# touche_client.net
KiCad netlist of a schematic drawn in EAGLE
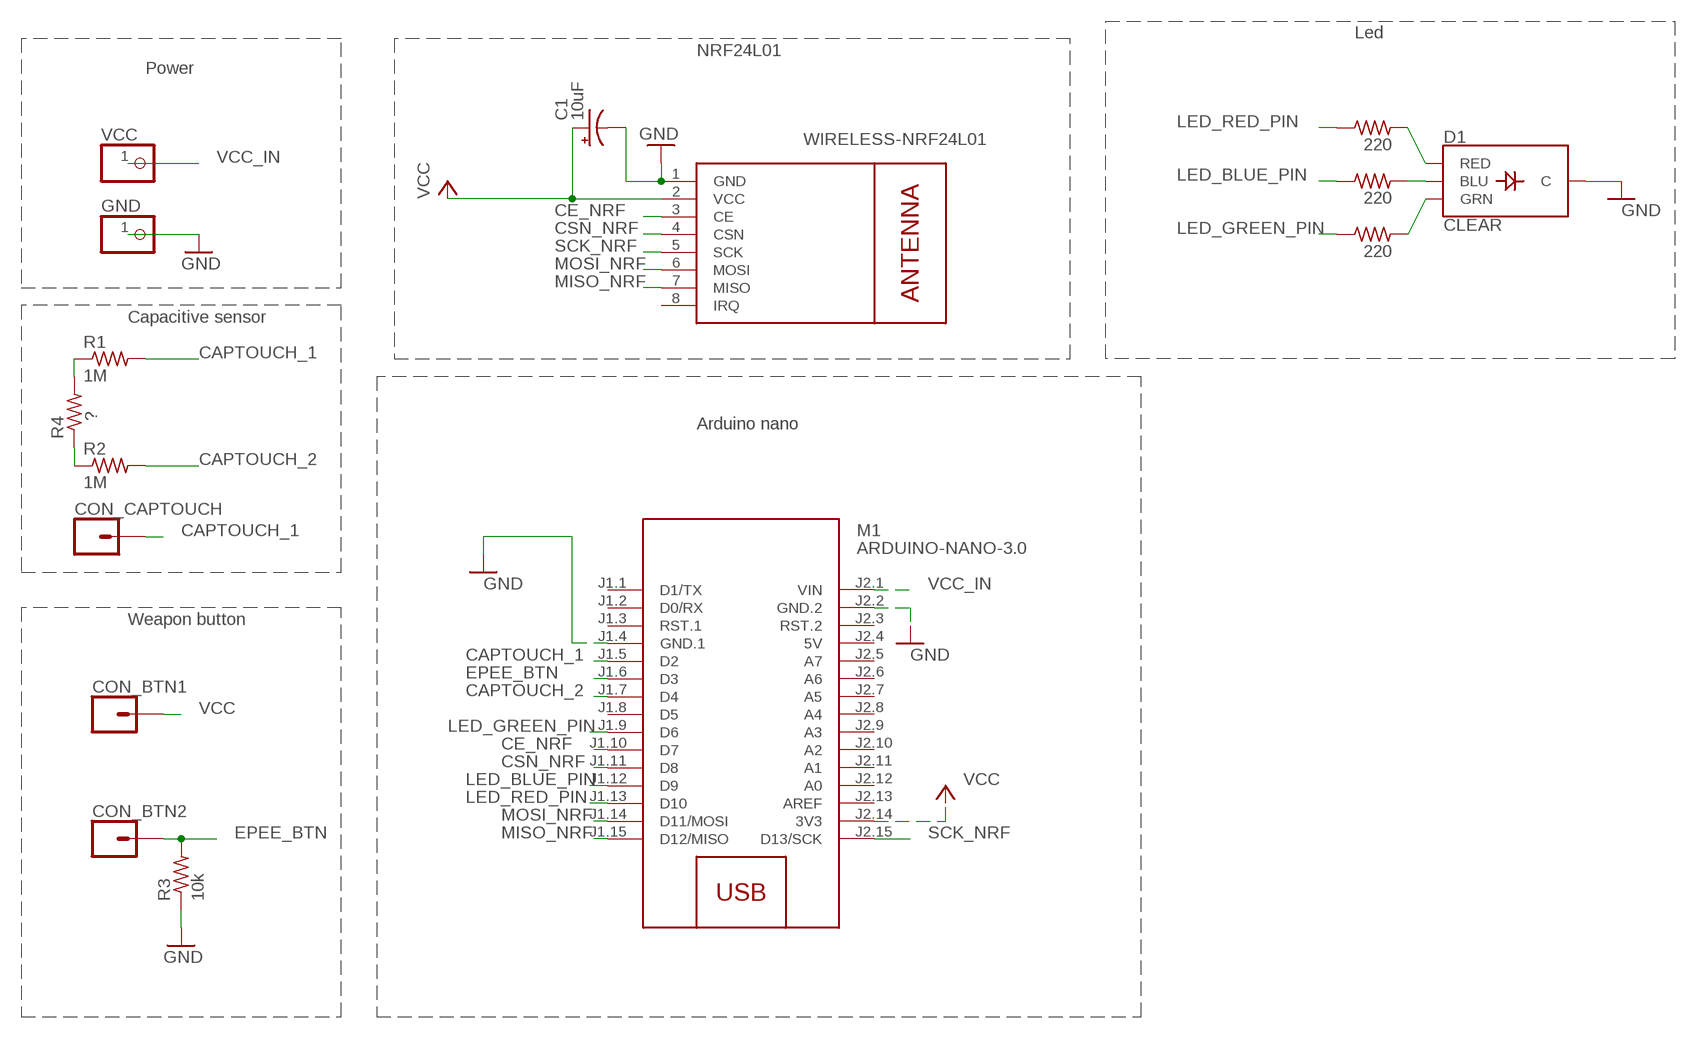
[diagram p0: schematic, sheet 1]

(export (version "E")
  (design (tool "Eeschema 10.0.6"))
  (components
    (comp (ref "C1")
      (value "10uF")
      (footprint "eagle-import:E2-5")
      (libsource (lib "eagle-import") (part "CPOL-USE2-5"))
    )
    (comp (ref "CON_BTN1")
      (value "CONN_01")
      (footprint "eagle-import:1X01")
      (libsource (lib "eagle-import") (part "CONN_01"))
    )
    (comp (ref "CON_BTN2")
      (value "CONN_01")
      (footprint "eagle-import:1X01")
      (libsource (lib "eagle-import") (part "CONN_01"))
    )
    (comp (ref "CON_CAPTOUCH")
      (value "CONN_01")
      (footprint "eagle-import:1X01")
      (libsource (lib "eagle-import") (part "CONN_01"))
    )
    (comp (ref "D1")
      (value "CLEAR")
      (footprint "eagle-import:LED-RGB-THRU")
      (libsource (lib "eagle-import") (part "LED-RGB-CCCLEAR"))
    )
    (comp (ref "GND")
      (value "PINHD-1X1")
      (footprint "eagle-import:1X01")
      (libsource (lib "eagle-import") (part "PINHD-1X1"))
    )
    (comp (ref "M1")
      (value "ARDUINO-NANO-3.0")
      (footprint "eagle-import:ARDUINO-NANO-3.0")
      (libsource (lib "eagle-import") (part "ARDUINO-NANO-3.0"))
    )
    (comp (ref "M2")
      (value "WIRELESS-NRF24L01")
      (footprint "eagle-import:WIRELESS-NRF24L01")
      (libsource (lib "eagle-import") (part "WIRELESS-NRF24L01"))
    )
    (comp (ref "R1")
      (value "1M")
      (footprint "eagle-import:0204_7")
      (libsource (lib "eagle-import") (part "R-US_0204/7"))
    )
    (comp (ref "R2")
      (value "1M")
      (footprint "eagle-import:0204_7")
      (libsource (lib "eagle-import") (part "R-US_0204/7"))
    )
    (comp (ref "R3")
      (value "10k")
      (footprint "eagle-import:0204_7")
      (libsource (lib "eagle-import") (part "R-US_0204/7"))
    )
    (comp (ref "R4")
      (value "?")
      (footprint "eagle-import:0204_7")
      (libsource (lib "eagle-import") (part "R-US_0204/7"))
    )
    (comp (ref "R_LED1")
      (value "220")
      (footprint "eagle-import:0204_7")
      (libsource (lib "eagle-import") (part "R-US_0204/7"))
    )
    (comp (ref "R_LED2")
      (value "220")
      (footprint "eagle-import:0204_7")
      (libsource (lib "eagle-import") (part "R-US_0204/7"))
    )
    (comp (ref "R_LED3")
      (value "220")
      (footprint "eagle-import:0204_7")
      (libsource (lib "eagle-import") (part "R-US_0204/7"))
    )
    (comp (ref "VCC")
      (value "PINHD-1X1")
      (footprint "eagle-import:1X01")
      (libsource (lib "eagle-import") (part "PINHD-1X1"))
    )
  )
  (nets
    (net (code "1") (name "/5V") (class "Default")
      (node (ref "M1") (pin "J2.4") (pinfunction "5V_J2.4") (pintype "power_in"))
    )
    (net (code "2") (name "/CAPTOUCH_1") (class "Default")
      (node (ref "CON_CAPTOUCH") (pin "1") (pinfunction "1_1") (pintype "passive"))
      (node (ref "M1") (pin "J1.5") (pinfunction "D2_J1.5") (pintype "bidirectional"))
      (node (ref "R1") (pin "2") (pinfunction "2_2") (pintype "passive"))
    )
    (net (code "3") (name "/CAPTOUCH_2") (class "Default")
      (node (ref "M1") (pin "J1.7") (pinfunction "D4_J1.7") (pintype "bidirectional"))
      (node (ref "R2") (pin "2") (pinfunction "2_2") (pintype "passive"))
    )
    (net (code "4") (name "/CE_NRF") (class "Default")
      (node (ref "M1") (pin "J1.10") (pinfunction "D7_J1.10") (pintype "bidirectional"))
      (node (ref "M2") (pin "3") (pinfunction "CE_3") (pintype "bidirectional"))
    )
    (net (code "5") (name "/CSN_NRF") (class "Default")
      (node (ref "M1") (pin "J1.11") (pinfunction "D8_J1.11") (pintype "bidirectional"))
      (node (ref "M2") (pin "4") (pinfunction "CSN_4") (pintype "bidirectional"))
    )
    (net (code "6") (name "/EPEE_BTN") (class "Default")
      (node (ref "CON_BTN2") (pin "1") (pinfunction "1_1") (pintype "passive"))
      (node (ref "M1") (pin "J1.6") (pinfunction "D3_J1.6") (pintype "bidirectional"))
      (node (ref "R3") (pin "2") (pinfunction "2_2") (pintype "passive"))
    )
    (net (code "7") (name "/LED_BLUE_PIN") (class "Default")
      (node (ref "M1") (pin "J1.12") (pinfunction "D9_J1.12") (pintype "bidirectional"))
      (node (ref "R_LED2") (pin "1") (pinfunction "1_1") (pintype "passive"))
    )
    (net (code "8") (name "/LED_GREEN_PIN") (class "Default")
      (node (ref "M1") (pin "J1.9") (pinfunction "D6_J1.9") (pintype "bidirectional"))
      (node (ref "R_LED3") (pin "1") (pinfunction "1_1") (pintype "passive"))
    )
    (net (code "9") (name "/LED_RED_PIN") (class "Default")
      (node (ref "M1") (pin "J1.13") (pinfunction "D10_J1.13") (pintype "bidirectional"))
      (node (ref "R_LED1") (pin "1") (pinfunction "1_1") (pintype "passive"))
    )
    (net (code "10") (name "/MISO_NRF") (class "Default")
      (node (ref "M1") (pin "J1.15") (pinfunction "D12/MISO_J1.15") (pintype "bidirectional"))
      (node (ref "M2") (pin "7") (pinfunction "MISO_7") (pintype "bidirectional"))
    )
    (net (code "11") (name "/MOSI_NRF") (class "Default")
      (node (ref "M1") (pin "J1.14") (pinfunction "D11/MOSI_J1.14") (pintype "bidirectional"))
      (node (ref "M2") (pin "6") (pinfunction "MOSI_6") (pintype "bidirectional"))
    )
    (net (code "12") (name "/SCK_NRF") (class "Default")
      (node (ref "M1") (pin "J2.15") (pinfunction "D13/SCK_J2.15") (pintype "bidirectional"))
      (node (ref "M2") (pin "5") (pinfunction "SCK_5") (pintype "bidirectional"))
    )
    (net (code "13") (name "/VCC_IN") (class "Default")
      (node (ref "M1") (pin "J2.1") (pinfunction "VIN_J2.1") (pintype "power_in"))
      (node (ref "VCC") (pin "1") (pinfunction "1_1") (pintype "passive"))
    )
    (net (code "14") (name "GND") (class "Default")
      (node (ref "C1") (pin "-") (pinfunction "-_-") (pintype "passive"))
      (node (ref "D1") (pin "2") (pinfunction "C_2") (pintype "bidirectional"))
      (node (ref "GND") (pin "1") (pinfunction "1_1") (pintype "passive"))
      (node (ref "M1") (pin "J1.4") (pinfunction "GND.1_J1.4") (pintype "power_in"))
      (node (ref "M1") (pin "J2.2") (pinfunction "GND.2_J2.2") (pintype "power_in"))
      (node (ref "M2") (pin "1") (pinfunction "GND_1") (pintype "power_in"))
      (node (ref "R3") (pin "1") (pinfunction "1_1") (pintype "passive"))
    )
    (net (code "15") (name "Net-(D1-BLU)") (class "Default")
      (node (ref "D1") (pin "4") (pinfunction "BLU_4") (pintype "bidirectional"))
      (node (ref "R_LED2") (pin "2") (pinfunction "2_2") (pintype "passive"))
    )
    (net (code "16") (name "Net-(D1-GRN)") (class "Default")
      (node (ref "D1") (pin "3") (pinfunction "GRN_3") (pintype "bidirectional"))
      (node (ref "R_LED3") (pin "2") (pinfunction "2_2") (pintype "passive"))
    )
    (net (code "17") (name "Net-(D1-RED)") (class "Default")
      (node (ref "D1") (pin "1") (pinfunction "RED_1") (pintype "bidirectional"))
      (node (ref "R_LED1") (pin "2") (pinfunction "2_2") (pintype "passive"))
    )
    (net (code "18") (name "Net-(R1-Pad1)") (class "Default")
      (node (ref "R1") (pin "1") (pinfunction "1_1") (pintype "passive"))
      (node (ref "R4") (pin "2") (pinfunction "2_2") (pintype "passive"))
    )
    (net (code "19") (name "Net-(R2-Pad1)") (class "Default")
      (node (ref "R2") (pin "1") (pinfunction "1_1") (pintype "passive"))
      (node (ref "R4") (pin "1") (pinfunction "1_1") (pintype "passive"))
    )
    (net (code "20") (name "VCC") (class "Default")
      (node (ref "C1") (pin "+") (pinfunction "+_+") (pintype "passive"))
      (node (ref "CON_BTN1") (pin "1") (pinfunction "1_1") (pintype "passive"))
      (node (ref "M1") (pin "J2.14") (pinfunction "3V3_J2.14") (pintype "power_in"))
      (node (ref "M2") (pin "2") (pinfunction "VCC_2") (pintype "power_in"))
    )
    (net (code "21") (name "unconnected-(M1-A0-PadJ2.12)") (class "Default")
      (node (ref "M1") (pin "J2.12") (pinfunction "A0_J2.12") (pintype "bidirectional"))
    )
    (net (code "22") (name "unconnected-(M1-A1-PadJ2.11)") (class "Default")
      (node (ref "M1") (pin "J2.11") (pinfunction "A1_J2.11") (pintype "bidirectional"))
    )
    (net (code "23") (name "unconnected-(M1-A2-PadJ2.10)") (class "Default")
      (node (ref "M1") (pin "J2.10") (pinfunction "A2_J2.10") (pintype "bidirectional"))
    )
    (net (code "24") (name "unconnected-(M1-A3-PadJ2.9)") (class "Default")
      (node (ref "M1") (pin "J2.9") (pinfunction "A3_J2.9") (pintype "bidirectional"))
    )
    (net (code "25") (name "unconnected-(M1-A4-PadJ2.8)") (class "Default")
      (node (ref "M1") (pin "J2.8") (pinfunction "A4_J2.8") (pintype "bidirectional"))
    )
    (net (code "26") (name "unconnected-(M1-A5-PadJ2.7)") (class "Default")
      (node (ref "M1") (pin "J2.7") (pinfunction "A5_J2.7") (pintype "bidirectional"))
    )
    (net (code "27") (name "unconnected-(M1-A6-PadJ2.6)") (class "Default")
      (node (ref "M1") (pin "J2.6") (pinfunction "A6_J2.6") (pintype "bidirectional"))
    )
    (net (code "28") (name "unconnected-(M1-A7-PadJ2.5)") (class "Default")
      (node (ref "M1") (pin "J2.5") (pinfunction "A7_J2.5") (pintype "bidirectional"))
    )
    (net (code "29") (name "unconnected-(M1-AREF-PadJ2.13)") (class "Default")
      (node (ref "M1") (pin "J2.13") (pinfunction "AREF_J2.13") (pintype "bidirectional"))
    )
    (net (code "30") (name "unconnected-(M1-D0{slash}RX-PadJ1.2)") (class "Default")
      (node (ref "M1") (pin "J1.2") (pinfunction "D0/RX_J1.2") (pintype "bidirectional"))
    )
    (net (code "31") (name "unconnected-(M1-D1{slash}TX-PadJ1.1)") (class "Default")
      (node (ref "M1") (pin "J1.1") (pinfunction "D1/TX_J1.1") (pintype "bidirectional"))
    )
    (net (code "32") (name "unconnected-(M1-D5-PadJ1.8)") (class "Default")
      (node (ref "M1") (pin "J1.8") (pinfunction "D5_J1.8") (pintype "bidirectional"))
    )
    (net (code "33") (name "unconnected-(M1-RST.1-PadJ1.3)") (class "Default")
      (node (ref "M1") (pin "J1.3") (pinfunction "RST.1_J1.3") (pintype "bidirectional"))
    )
    (net (code "34") (name "unconnected-(M1-RST.2-PadJ2.3)") (class "Default")
      (node (ref "M1") (pin "J2.3") (pinfunction "RST.2_J2.3") (pintype "bidirectional"))
    )
    (net (code "35") (name "unconnected-(M2-IRQ-Pad8)") (class "Default")
      (node (ref "M2") (pin "8") (pinfunction "IRQ_8") (pintype "bidirectional"))
    )
  )
)
